# ActuatorMKII_Circuits.net
KiCad netlist of a schematic drawn in Altium Designer
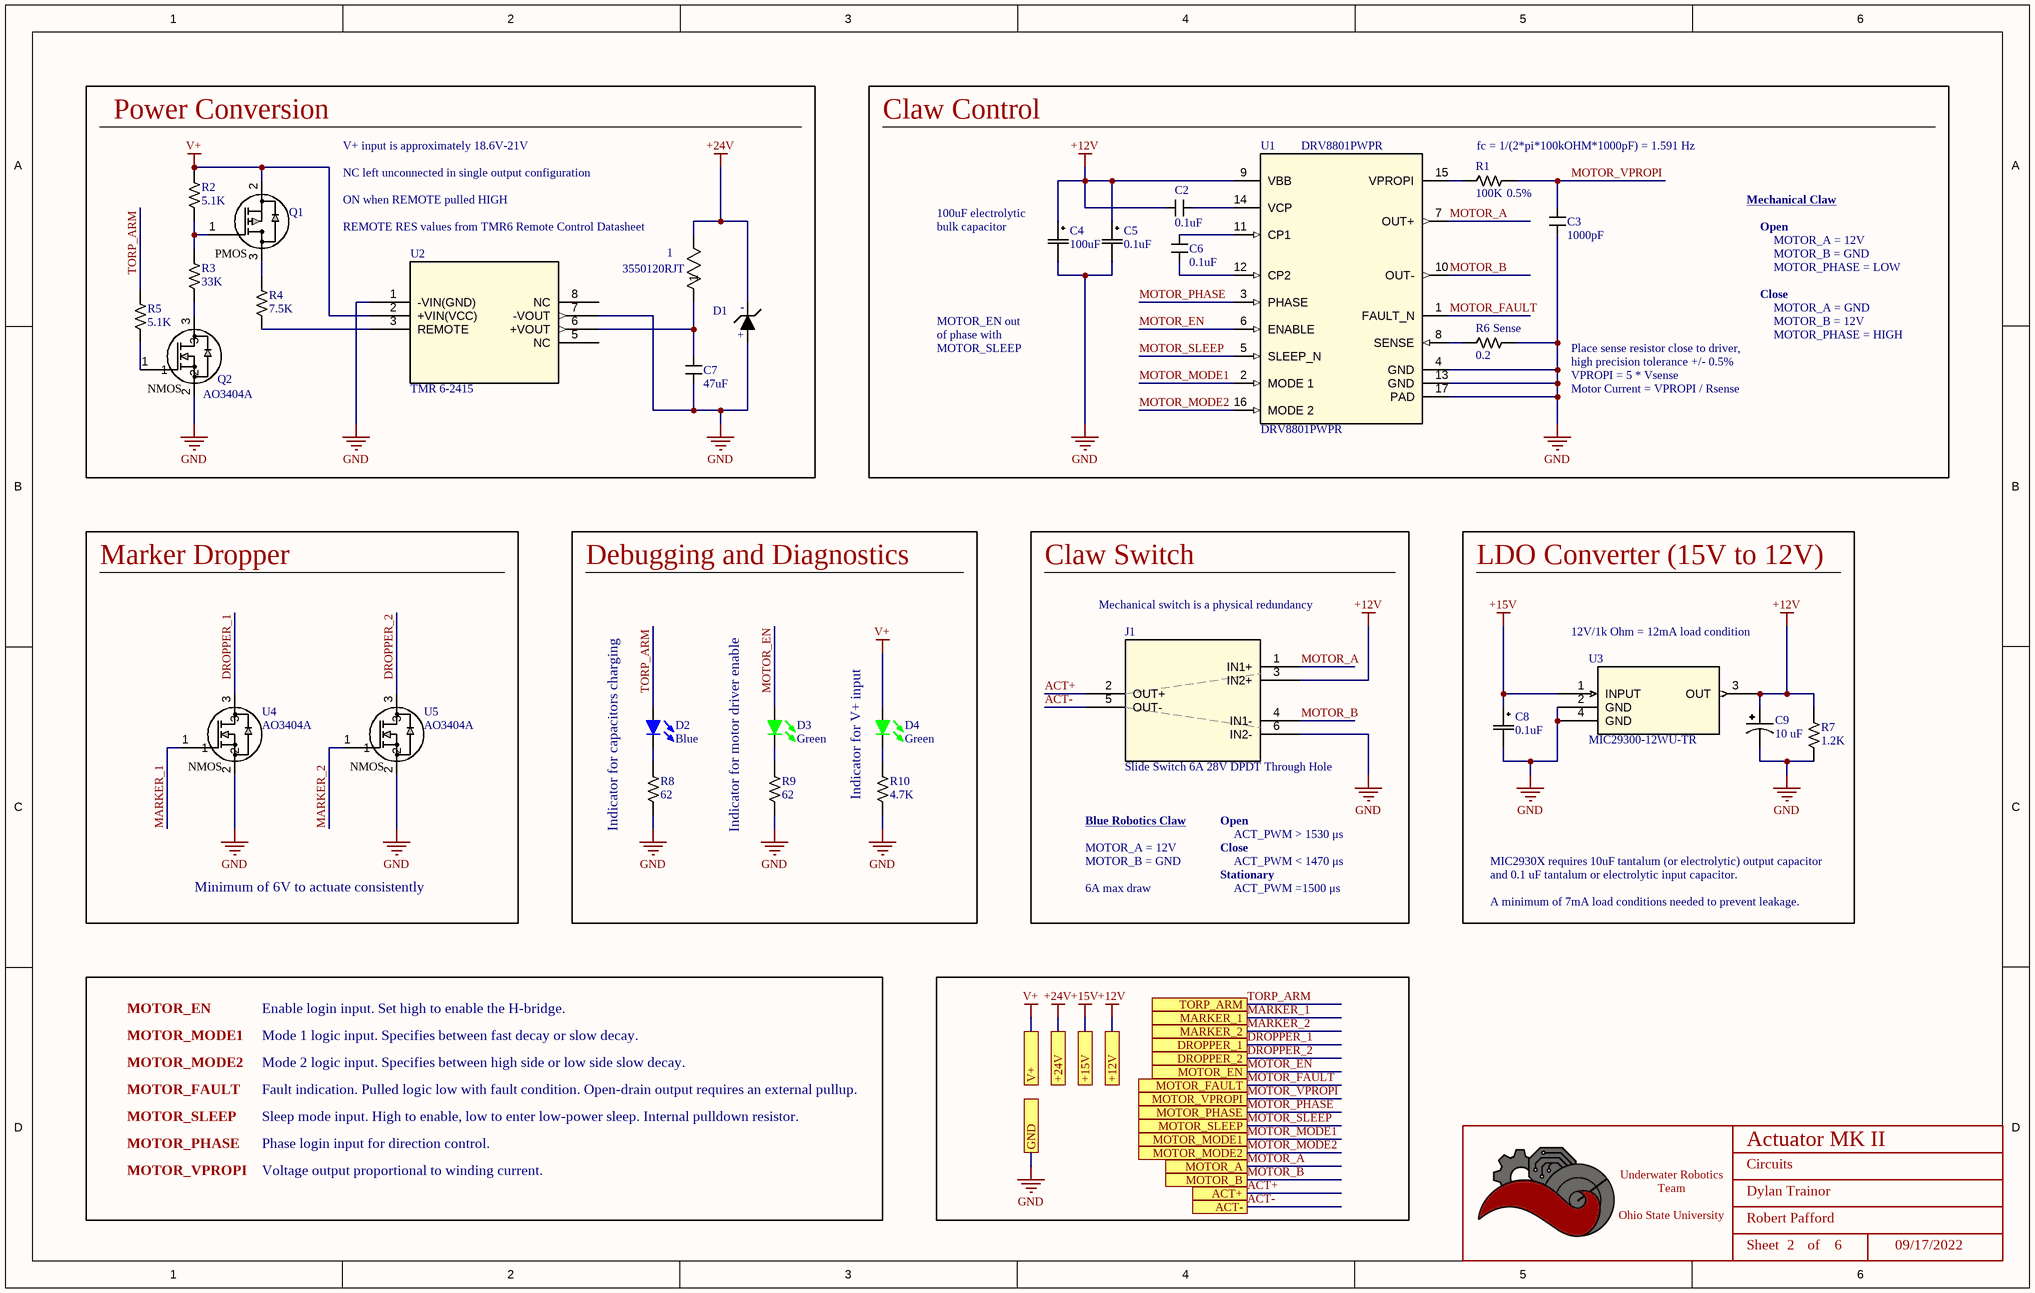
[diagram p0: ActuatorMKII_Circuits.SchDoc]

(export (version "E")
  (design (tool "Eeschema 10.0.6"))
  (components
    (comp (ref "1")
      (value "3550120RJT")
      (footprint "RES_3550_TEC")
      (description "RES 3550 120R 5%")
      (fields (field (name "COPYRIGHT") "Copyright (C) 2022 Ultra Librarian. All rights reserved."))
      (libsource (lib "Resistors") (part "3550120RJT"))
    )
    (comp (ref "C2")
      (value "0.1uF")
      (footprint "CAPACITOR_0805")
      (description "Cap 100nF 50V +/-10%\r\nCeramic 0805")
      (fields
        (field (name "TOLERANCE") "+/- 10%")
        (field (name "VOLTAGE") "25V")
        (field (name "MADE BY") "Robert Pafford")
      )
      (libsource (lib "Capacitors") (part "CAPACITOR_0.1uF_0402_1"))
    )
    (comp (ref "C3")
      (value "1000pF")
      (footprint "CAPACITOR_0603")
      (description "Cap 1000pF 50V +/-2%\r\nCeramic 0603")
      (fields
        (field (name "TOLERANCE") "+/- 2%")
        (field (name "VOLTAGE") "50")
        (field (name "MADE BY") "Flip B")
      )
      (libsource (lib "Capacitors") (part "CAPACITOR_0.001uF_0603"))
    )
    (comp (ref "C4")
      (value "100uF")
      (footprint "PCAP_8x5.4-ELECT_NCA")
      (description "100 µF 35 V Aluminum Electrolytic Capacitors Radial, Can - SMD 1000 Hrs")
      (fields
        (field (name "MANUFACTURER_PART_NUMBER") "UCB1V0R1MCL1GS")
        (field (name "Comment") "100uF electrolytic 35 V")
        (field (name "COPYRIGHT") "Copyright (C) 2022 Ultra Librarian. All rights reserved.")
        (field (name "MADE BY") "Tyson Nguyen")
      )
      (libsource (lib "Capacitors") (part "CAP ALUM 100UF 20% 35V SMD"))
    )
    (comp (ref "C5")
      (value "0.1uF")
      (footprint "U2-D_NCH")
      (description "0.1 µF 35 V Aluminum Electrolytic Capacitors Radial, Can - SMD 7000 Hrs @ 105°C")
      (fields
        (field (name "MANUFACTURER_PART_NUMBER") "UCB1V0R1MCL1GS")
        (field (name "Comment") "0.1uF electrolytic 35 V")
        (field (name "COPYRIGHT") "Copyright (C) 2022 Ultra Librarian. All rights reserved.")
        (field (name "MADE BY") "Tyson Nguyen")
      )
      (libsource (lib "Capacitors") (part "CAP ALUM 0.1UF 20% 35V SMD"))
    )
    (comp (ref "C6")
      (value "0.1uF")
      (footprint "CAPACITOR_0805")
      (description "Cap 100nF 50V +/-10%\r\nCeramic 0805")
      (fields
        (field (name "TOLERANCE") "+/- 10%")
        (field (name "VOLTAGE") "25V")
        (field (name "MADE BY") "Robert Pafford")
      )
      (libsource (lib "Capacitors") (part "CAPACITOR_0.1uF_0402_1"))
    )
    (comp (ref "C7")
      (value "47uF")
      (footprint "PCAP_8x5.4-ELECT_NCA")
      (description "CAP ALUM 47uF 50V +/-20%\r\n8x5.4")
      (fields
        (field (name "TOLERANCE") "+/- 20%")
        (field (name "VOLTAGE") "6.3V")
        (field (name "MADE BY") "Flip B")
      )
      (libsource (lib "Capacitors") (part "CAP_ALUM_47uF"))
    )
    (comp (ref "C8")
      (value "0.1uF")
      (footprint "U2-D_NCH")
      (description "0.1 µF 35 V Aluminum Electrolytic Capacitors Radial, Can - SMD 7000 Hrs @ 105°C")
      (fields
        (field (name "MANUFACTURER_PART_NUMBER") "UCB1V0R1MCL1GS")
        (field (name "Comment") "0.1uF electrolytic 35 V")
        (field (name "COPYRIGHT") "Copyright (C) 2022 Ultra Librarian. All rights reserved.")
        (field (name "MADE BY") "Tyson Nguyen")
      )
      (libsource (lib "Capacitors") (part "CAP ALUM 0.1UF 20% 35V SMD"))
    )
    (comp (ref "C9")
      (value "10uF Tantalum 16V")
      (footprint "CAPACITOR_1206 - POLAR")
      (description "Cap 10uF 16V +/-20%\r\nTantalum 1206")
      (fields
        (field (name "TOLERANCE") "+/- 10%")
        (field (name "VOLTAGE") "16V")
        (field (name "VALUE (UF)") "10 uF")
        (field (name "MADE BY") "Dylan T")
      )
      (libsource (lib "Capacitors") (part "CAPACITOR_10uF_1206_Tantalum_1"))
    )
    (comp (ref "D1")
      (value "Zener_Diode_10V_410mW")
      (footprint "SOD-123")
      (description "Zener Diode ¦ 10 V ¦ 410 mW ¦ SOD 123")
      (fields (field (name "POWER") "410mW") (field (name "MADE BY") "Nathan A"))
      (libsource (lib "Diodes") (part "Zener_Diode_10V_410mW"))
    )
    (comp (ref "D2")
      (value "150060BS75000")
      (footprint "LED_0603")
      (description "LED Blue Vf= 3.2V If = 0.020A\r\n150060BS75000")
      (fields (field (name "COLOR") "Blue") (field (name "MADE BY") "Robert Pafford"))
      (libsource (lib "Diodes") (part "LED_Blue_0603"))
    )
    (comp (ref "D3")
      (value "IN-S63AT5G")
      (footprint "LED_0603")
      (description "LED Green Vf= 3V If = 0.005A\r\nIN-S63AT5G")
      (fields (field (name "COLOR") "Green") (field (name "MADE BY") "Robert Pafford"))
      (libsource (lib "Diodes") (part "LED_Green_0603_3V"))
    )
    (comp (ref "D4")
      (value "IN-S63AT5G")
      (footprint "LED_0603")
      (description "LED Green Vf= 3V If = 0.005A\r\nIN-S63AT5G")
      (fields (field (name "COLOR") "Green") (field (name "MADE BY") "Robert Pafford"))
      (libsource (lib "Diodes") (part "LED_Green_0603_3V"))
    )
    (comp (ref "J1")
      (value "Slide Switch 6A 28V DPDT Through Hole")
      (footprint "CONN_S3CQE2")
      (description "SWITCH SLIDE DPDT 6A 28V Through Hole")
      (fields
        (field (name "MANUFACTURER_PART_NUMBER") "1201M2S3CQE2")
        (field (name "COPYRIGHT") "Copyright (C) 2022 Ultra Librarian. All rights reserved.")
      )
      (libsource (lib "Switches") (part "Slide DPDT Switch"))
    )
    (comp (ref "Q1")
      (value "DMP3056L-7")
      (footprint "SOT-23-3")
      (description "P-Channel 30V 4.3A (Ta) 1.38W (Ta) Surface Mount SOT23")
      (fields (field (name "CREATED BY") "John Ulm") (field (name "REVIEWED BY") "---"))
      (libsource (lib "Transistors") (part "DMP3056L-7"))
    )
    (comp (ref "Q2")
      (value "AO3404A")
      (footprint "SOT-23-3")
      (description "N-Channel 30 V 5.8A (Ta) 1.4W (Ta) Surface Mount SOT-23-3")
      (fields (field (name "CREATED BY") "Dylan T"))
      (libsource (lib "Transistors") (part "AO3404A"))
    )
    (comp (ref "R1")
      (value "100k Ohm 5% 1/8W")
      (footprint "RESISTOR_0603")
      (description "RES 100k OHM 5% 1/10W 0603")
      (fields
        (field (name "TOLERANCE") "+/- 5%")
        (field (name "VALUE  (OHMS)") "100K")
        (field (name "MADE BY") "Flip B")
      )
      (libsource (lib "Resistors") (part "RESISTOR_100K_0603_1"))
    )
    (comp (ref "R2")
      (value "5.1k Ohm 1% 1/8W")
      (footprint "RESISTOR_0805")
      (description "RES 5.1k OHM 1% 1/8W 0805")
      (fields
        (field (name "TOLERANCE") "+/- 5%")
        (field (name "VALUE  (OHMS)") "5.1K")
        (field (name "MADE BY") "Dylan Trainor")
      )
      (libsource (lib "Resistors") (part "RESISTOR_5.1K_0805"))
    )
    (comp (ref "R3")
      (value "33k Ohm 5% 1/8W")
      (footprint "RESISTOR_0805")
      (description "RES 33k OHM 5% 1/8W 0805")
      (fields
        (field (name "TOLERANCE") "+/- 5%")
        (field (name "VALUE  (OHMS)") "33K")
        (field (name "MADE BY") "Dylan Trainor")
      )
      (libsource (lib "Resistors") (part "RESISTOR_33K_0805"))
    )
    (comp (ref "R4")
      (value "7.5k Ohm 5% 1/10W")
      (footprint "RESISTOR_0603")
      (description "RES 7.5k OHM 5% 1/10W 0603")
      (fields
        (field (name "TOLERANCE") "+/- 5%")
        (field (name "VALUE  (OHMS)") "7.5K")
        (field (name "MADE BY") "Dylan Trainor")
      )
      (libsource (lib "Resistors") (part "RESISTOR_7.5K_0603"))
    )
    (comp (ref "R5")
      (value "5.1k Ohm 1% 1/8W")
      (footprint "RESISTOR_0805")
      (description "RES 5.1k OHM 1% 1/8W 0805")
      (fields
        (field (name "TOLERANCE") "+/- 5%")
        (field (name "VALUE  (OHMS)") "5.1K")
        (field (name "MADE BY") "Dylan Trainor")
      )
      (libsource (lib "Resistors") (part "RESISTOR_5.1K_0805"))
    )
    (comp (ref "R6")
      (value "0.2 Ohm 1% 2W 2512")
      (footprint "RESISTOR_2512")
      (description "RES 0.2 OHM 1% 2W 2512")
      (fields
        (field (name "TOLERANCE") "+/- 1%")
        (field (name "VALUE  (OHMS)") "0.2")
        (field (name "MADE BY") "Dylan Trainor")
      )
      (libsource (lib "Resistors") (part "RESISTOR_0.2_1%_2512"))
    )
    (comp (ref "R7")
      (value "1.2k Ohm 5% 1/2W")
      (footprint "RESISTOR_0805")
      (description "RES 1.2k OHM 5% 1/2W 0805")
      (fields
        (field (name "TOLERANCE") "+/- 5%")
        (field (name "VALUE  (OHMS)") "1.2K")
        (field (name "MADE BY") "Robert Pafford")
      )
      (libsource (lib "Resistors") (part "RESISTOR_1.2K_0805"))
    )
    (comp (ref "R8")
      (value "62 Ohm 1% 1/4W")
      (footprint "RESISTOR_0603")
      (description "RES SMD 62 OHM 1% 1/4W 0603")
      (fields
        (field (name "TOLERANCE") "+/- 1%")
        (field (name "VALUE  (OHMS)") "62")
        (field (name "MADE BY") "Robert Pafford")
      )
      (libsource (lib "Resistors") (part "RESISTOR_62_0603"))
    )
    (comp (ref "R9")
      (value "62 Ohm 1% 1/4W")
      (footprint "RESISTOR_0603")
      (description "RES SMD 62 OHM 1% 1/4W 0603")
      (fields
        (field (name "TOLERANCE") "+/- 1%")
        (field (name "VALUE  (OHMS)") "62")
        (field (name "MADE BY") "Robert Pafford")
      )
      (libsource (lib "Resistors") (part "RESISTOR_62_0603"))
    )
    (comp (ref "R10")
      (value "4.7k Ohm 5% 1/10W")
      (footprint "RESISTOR_0603")
      (description "RES 4.7k OHM 5% 1/10W 0603")
      (fields
        (field (name "TOLERANCE") "+/- 5%")
        (field (name "VALUE  (OHMS)") "4.7K")
        (field (name "MADE BY") "Robert Pafford")
      )
      (libsource (lib "Resistors") (part "RESISTOR_4.7K_0603"))
    )
    (comp (ref "U1")
      (value "DRV8801PWPR")
      (footprint "PWP0016B")
      (description "Bipolar Motor Driver DMOS Parallel 16-HTSSOP")
      (fields
        (field (name "PARTNUMBER") "DRV8801PWP")
        (field (name "MANUFACTURER") "Texas Instruments")
        (field (name "COPYRIGHT") "Copyright (C) 2022 Ultra Librarian. All rights reserved.")
      )
      (libsource (lib "Integrated Circuits") (part "DRV8801PWPR"))
    )
    (comp (ref "U2")
      (value "TMR 6-2415")
      (footprint "TMR 6_TRP")
      (description "No Description Available")
      (fields (field (name "COPYRIGHT") "Copyright (C) 2022 Ultra Librarian. All rights reserved."))
      (libsource (lib "Converter") (part "TMR 6-2415"))
    )
    (comp (ref "U3")
      (value "MIC29300-12WU-TR")
      (footprint "TO-263-3_MCH")
      (description "Linear Voltage Regulator IC Positive Fixed 1 Output 3A TO-263-3")
      (fields (field (name "COPYRIGHT") "Copyright (C) 2022 Ultra Librarian. All rights reserved."))
      (libsource (lib "Converter") (part "MIC29300-12WU-TR"))
    )
    (comp (ref "U4")
      (value "AO3404A")
      (footprint "SOT-23-3")
      (description "N-Channel 30 V 5.8A (Ta) 1.4W (Ta) Surface Mount SOT-23-3")
      (fields (field (name "CREATED BY") "Dylan T"))
      (libsource (lib "Transistors") (part "AO3404A"))
    )
    (comp (ref "U5")
      (value "AO3404A")
      (footprint "SOT-23-3")
      (description "N-Channel 30 V 5.8A (Ta) 1.4W (Ta) Surface Mount SOT-23-3")
      (fields (field (name "CREATED BY") "Dylan T"))
      (libsource (lib "Transistors") (part "AO3404A"))
    )
  )
  (nets
    (net (code "1") (name "+12V") (class "Default")
      (node (ref "C2") (pin "2") (pinfunction "2_2") (pintype "passive"))
      (node (ref "C4") (pin "1") (pinfunction "1_1") (pintype "passive"))
      (node (ref "C5") (pin "1") (pinfunction "1_1") (pintype "passive"))
      (node (ref "C9") (pin "1") (pintype "passive"))
      (node (ref "J1") (pin "3") (pinfunction "IN2+_3") (pintype "passive"))
      (node (ref "R7") (pin "1") (pinfunction "1_1") (pintype "passive"))
      (node (ref "U1") (pin "9") (pinfunction "VBB_9") (pintype "power_in"))
      (node (ref "U3") (pin "3") (pinfunction "OUT_3") (pintype "output"))
    )
    (net (code "2") (name "+15V") (class "Default")
      (node (ref "C8") (pin "1") (pinfunction "1_1") (pintype "passive"))
      (node (ref "U3") (pin "1") (pinfunction "INPUT_1") (pintype "input"))
    )
    (net (code "3") (name "+24V") (class "Default")
      (node (ref "1") (pin "2") (pinfunction "2_2") (pintype "passive"))
      (node (ref "D1") (pin "2") (pinfunction "2_2") (pintype "passive"))
    )
    (net (code "4") (name "/ACT+") (class "Default")
      (node (ref "J1") (pin "2") (pinfunction "OUT+_2") (pintype "passive"))
    )
    (net (code "5") (name "/ACT-") (class "Default")
      (node (ref "J1") (pin "5") (pinfunction "OUT-_5") (pintype "passive"))
    )
    (net (code "6") (name "/DROPPER_1") (class "Default")
      (node (ref "U4") (pin "3") (pinfunction "3_3") (pintype "passive"))
    )
    (net (code "7") (name "/DROPPER_2") (class "Default")
      (node (ref "U5") (pin "3") (pinfunction "3_3") (pintype "passive"))
    )
    (net (code "8") (name "/MARKER_1") (class "Default")
      (node (ref "U4") (pin "1") (pinfunction "1_1") (pintype "passive"))
    )
    (net (code "9") (name "/MARKER_2") (class "Default")
      (node (ref "U5") (pin "1") (pinfunction "1_1") (pintype "passive"))
    )
    (net (code "10") (name "/MOTOR_A") (class "Default")
      (node (ref "J1") (pin "1") (pinfunction "IN1+_1") (pintype "passive"))
      (node (ref "U1") (pin "7") (pinfunction "OUT+_7") (pintype "output"))
    )
    (net (code "11") (name "/MOTOR_B") (class "Default")
      (node (ref "J1") (pin "4") (pinfunction "IN1-_4") (pintype "passive"))
      (node (ref "U1") (pin "10") (pinfunction "OUT-_10") (pintype "output"))
    )
    (net (code "12") (name "/MOTOR_EN") (class "Default")
      (node (ref "D3") (pin "1") (pinfunction "1_1") (pintype "passive"))
      (node (ref "U1") (pin "6") (pinfunction "ENABLE_6") (pintype "input"))
    )
    (net (code "13") (name "/MOTOR_FAULT") (class "Default")
      (node (ref "U1") (pin "1") (pinfunction "FAULT_N_1") (pintype "open_collector"))
    )
    (net (code "14") (name "/MOTOR_MODE1") (class "Default")
      (node (ref "U1") (pin "2") (pinfunction "MODE_1_2") (pintype "input"))
    )
    (net (code "15") (name "/MOTOR_MODE2") (class "Default")
      (node (ref "U1") (pin "16") (pinfunction "MODE_2_16") (pintype "input"))
    )
    (net (code "16") (name "/MOTOR_PHASE") (class "Default")
      (node (ref "U1") (pin "3") (pinfunction "PHASE_3") (pintype "input"))
    )
    (net (code "17") (name "/MOTOR_SLEEP") (class "Default")
      (node (ref "U1") (pin "5") (pinfunction "SLEEP_N_5") (pintype "input"))
    )
    (net (code "18") (name "/MOTOR_VPROPI") (class "Default")
      (node (ref "C3") (pin "1") (pinfunction "1_1") (pintype "passive"))
      (node (ref "R1") (pin "1") (pinfunction "1_1") (pintype "passive"))
    )
    (net (code "19") (name "/TORP_ARM") (class "Default")
      (node (ref "D2") (pin "1") (pinfunction "1_1") (pintype "passive"))
      (node (ref "R5") (pin "1") (pinfunction "1_1") (pintype "passive"))
    )
    (net (code "20") (name "GND") (class "Default")
      (node (ref "C3") (pin "2") (pinfunction "2_2") (pintype "passive"))
      (node (ref "C4") (pin "2") (pinfunction "2_2") (pintype "passive"))
      (node (ref "C5") (pin "2") (pinfunction "2_2") (pintype "passive"))
      (node (ref "C7") (pin "2") (pinfunction "2_2") (pintype "passive"))
      (node (ref "C8") (pin "2") (pinfunction "2_2") (pintype "passive"))
      (node (ref "C9") (pin "2") (pintype "passive"))
      (node (ref "D1") (pin "1") (pinfunction "1_1") (pintype "passive"))
      (node (ref "J1") (pin "6") (pinfunction "IN2-_6") (pintype "passive"))
      (node (ref "Q2") (pin "2") (pinfunction "2_2") (pintype "passive"))
      (node (ref "R10") (pin "2") (pinfunction "2_2") (pintype "passive"))
      (node (ref "R6") (pin "1") (pinfunction "1_1") (pintype "passive"))
      (node (ref "R7") (pin "2") (pinfunction "2_2") (pintype "passive"))
      (node (ref "R8") (pin "2") (pinfunction "2_2") (pintype "passive"))
      (node (ref "R9") (pin "2") (pinfunction "2_2") (pintype "passive"))
      (node (ref "U1") (pin "13") (pinfunction "GND_13") (pintype "power_in"))
      (node (ref "U1") (pin "17") (pinfunction "PAD_17") (pintype "power_in"))
      (node (ref "U1") (pin "4") (pinfunction "GND_4") (pintype "power_in"))
      (node (ref "U2") (pin "1") (pinfunction "-VIN(GND)_1") (pintype "power_in"))
      (node (ref "U2") (pin "7") (pinfunction "-VOUT_7") (pintype "output"))
      (node (ref "U3") (pin "2") (pinfunction "GND_2") (pintype "power_in"))
      (node (ref "U3") (pin "4") (pinfunction "GND_4") (pintype "power_in"))
      (node (ref "U4") (pin "2") (pinfunction "2_2") (pintype "passive"))
      (node (ref "U5") (pin "2") (pinfunction "2_2") (pintype "passive"))
    )
    (net (code "21") (name "Net-(D2-Pad2)") (class "Default")
      (node (ref "D2") (pin "2") (pinfunction "2_2") (pintype "passive"))
      (node (ref "R8") (pin "1") (pinfunction "1_1") (pintype "passive"))
    )
    (net (code "22") (name "Net-(D3-Pad2)") (class "Default")
      (node (ref "D3") (pin "2") (pinfunction "2_2") (pintype "passive"))
      (node (ref "R9") (pin "1") (pinfunction "1_1") (pintype "passive"))
    )
    (net (code "23") (name "Net-(D4-Pad2)") (class "Default")
      (node (ref "D4") (pin "2") (pinfunction "2_2") (pintype "passive"))
      (node (ref "R10") (pin "1") (pinfunction "1_1") (pintype "passive"))
    )
    (net (code "24") (name "Net-(Q1-Pad1)") (class "Default")
      (node (ref "Q1") (pin "1") (pinfunction "1_1") (pintype "passive"))
      (node (ref "R2") (pin "2") (pinfunction "2_2") (pintype "passive"))
      (node (ref "R3") (pin "1") (pinfunction "1_1") (pintype "passive"))
    )
    (net (code "25") (name "Net-(Q1-Pad3)") (class "Default")
      (node (ref "Q1") (pin "3") (pinfunction "3_3") (pintype "passive"))
      (node (ref "R4") (pin "1") (pinfunction "1_1") (pintype "passive"))
    )
    (net (code "26") (name "Net-(Q2-Pad1)") (class "Default")
      (node (ref "Q2") (pin "1") (pinfunction "1_1") (pintype "passive"))
      (node (ref "R5") (pin "2") (pinfunction "2_2") (pintype "passive"))
    )
    (net (code "27") (name "Net-(Q2-Pad3)") (class "Default")
      (node (ref "Q2") (pin "3") (pinfunction "3_3") (pintype "passive"))
      (node (ref "R3") (pin "2") (pinfunction "2_2") (pintype "passive"))
    )
    (net (code "28") (name "Net-(U1-CP1)") (class "Default")
      (node (ref "C6") (pin "1") (pinfunction "1_1") (pintype "passive"))
      (node (ref "U1") (pin "11") (pinfunction "CP1_11") (pintype "input"))
    )
    (net (code "29") (name "Net-(U1-CP2)") (class "Default")
      (node (ref "C6") (pin "2") (pinfunction "2_2") (pintype "passive"))
      (node (ref "U1") (pin "12") (pinfunction "CP2_12") (pintype "input"))
    )
    (net (code "30") (name "Net-(U1-SENSE)") (class "Default")
      (node (ref "R6") (pin "2") (pinfunction "2_2") (pintype "passive"))
      (node (ref "U1") (pin "8") (pinfunction "SENSE_8") (pintype "input"))
    )
    (net (code "31") (name "Net-(U1-VCP)") (class "Default")
      (node (ref "C2") (pin "1") (pinfunction "1_1") (pintype "passive"))
      (node (ref "U1") (pin "14") (pinfunction "VCP_14") (pintype "passive"))
    )
    (net (code "32") (name "Net-(U1-VPROPI)") (class "Default")
      (node (ref "R1") (pin "2") (pinfunction "2_2") (pintype "passive"))
      (node (ref "U1") (pin "15") (pinfunction "VPROPI_15") (pintype "power_in"))
    )
    (net (code "33") (name "Net-(U2-+VOUT)") (class "Default")
      (node (ref "1") (pin "1") (pinfunction "1_1") (pintype "passive"))
      (node (ref "C7") (pin "1") (pinfunction "1_1") (pintype "passive"))
      (node (ref "U2") (pin "6") (pinfunction "+VOUT_6") (pintype "output"))
    )
    (net (code "34") (name "Net-(U2-REMOTE)") (class "Default")
      (node (ref "R4") (pin "2") (pinfunction "2_2") (pintype "passive"))
      (node (ref "U2") (pin "3") (pinfunction "REMOTE_3") (pintype "passive"))
    )
    (net (code "35") (name "V+") (class "Default")
      (node (ref "D4") (pin "1") (pinfunction "1_1") (pintype "passive"))
      (node (ref "Q1") (pin "2") (pinfunction "2_2") (pintype "passive"))
      (node (ref "R2") (pin "1") (pinfunction "1_1") (pintype "passive"))
      (node (ref "U2") (pin "2") (pinfunction "+VIN(VCC)_2") (pintype "power_in"))
    )
    (net (code "36") (name "unconnected-(U2-NC-Pad5)") (class "Default")
      (node (ref "U2") (pin "5") (pinfunction "NC_5") (pintype "passive"))
    )
    (net (code "37") (name "unconnected-(U2-NC-Pad8)") (class "Default")
      (node (ref "U2") (pin "8") (pinfunction "NC_8") (pintype "passive"))
    )
  )
)
